# video_board_yis503.net
KiCad netlist of a schematic drawn in EAGLE
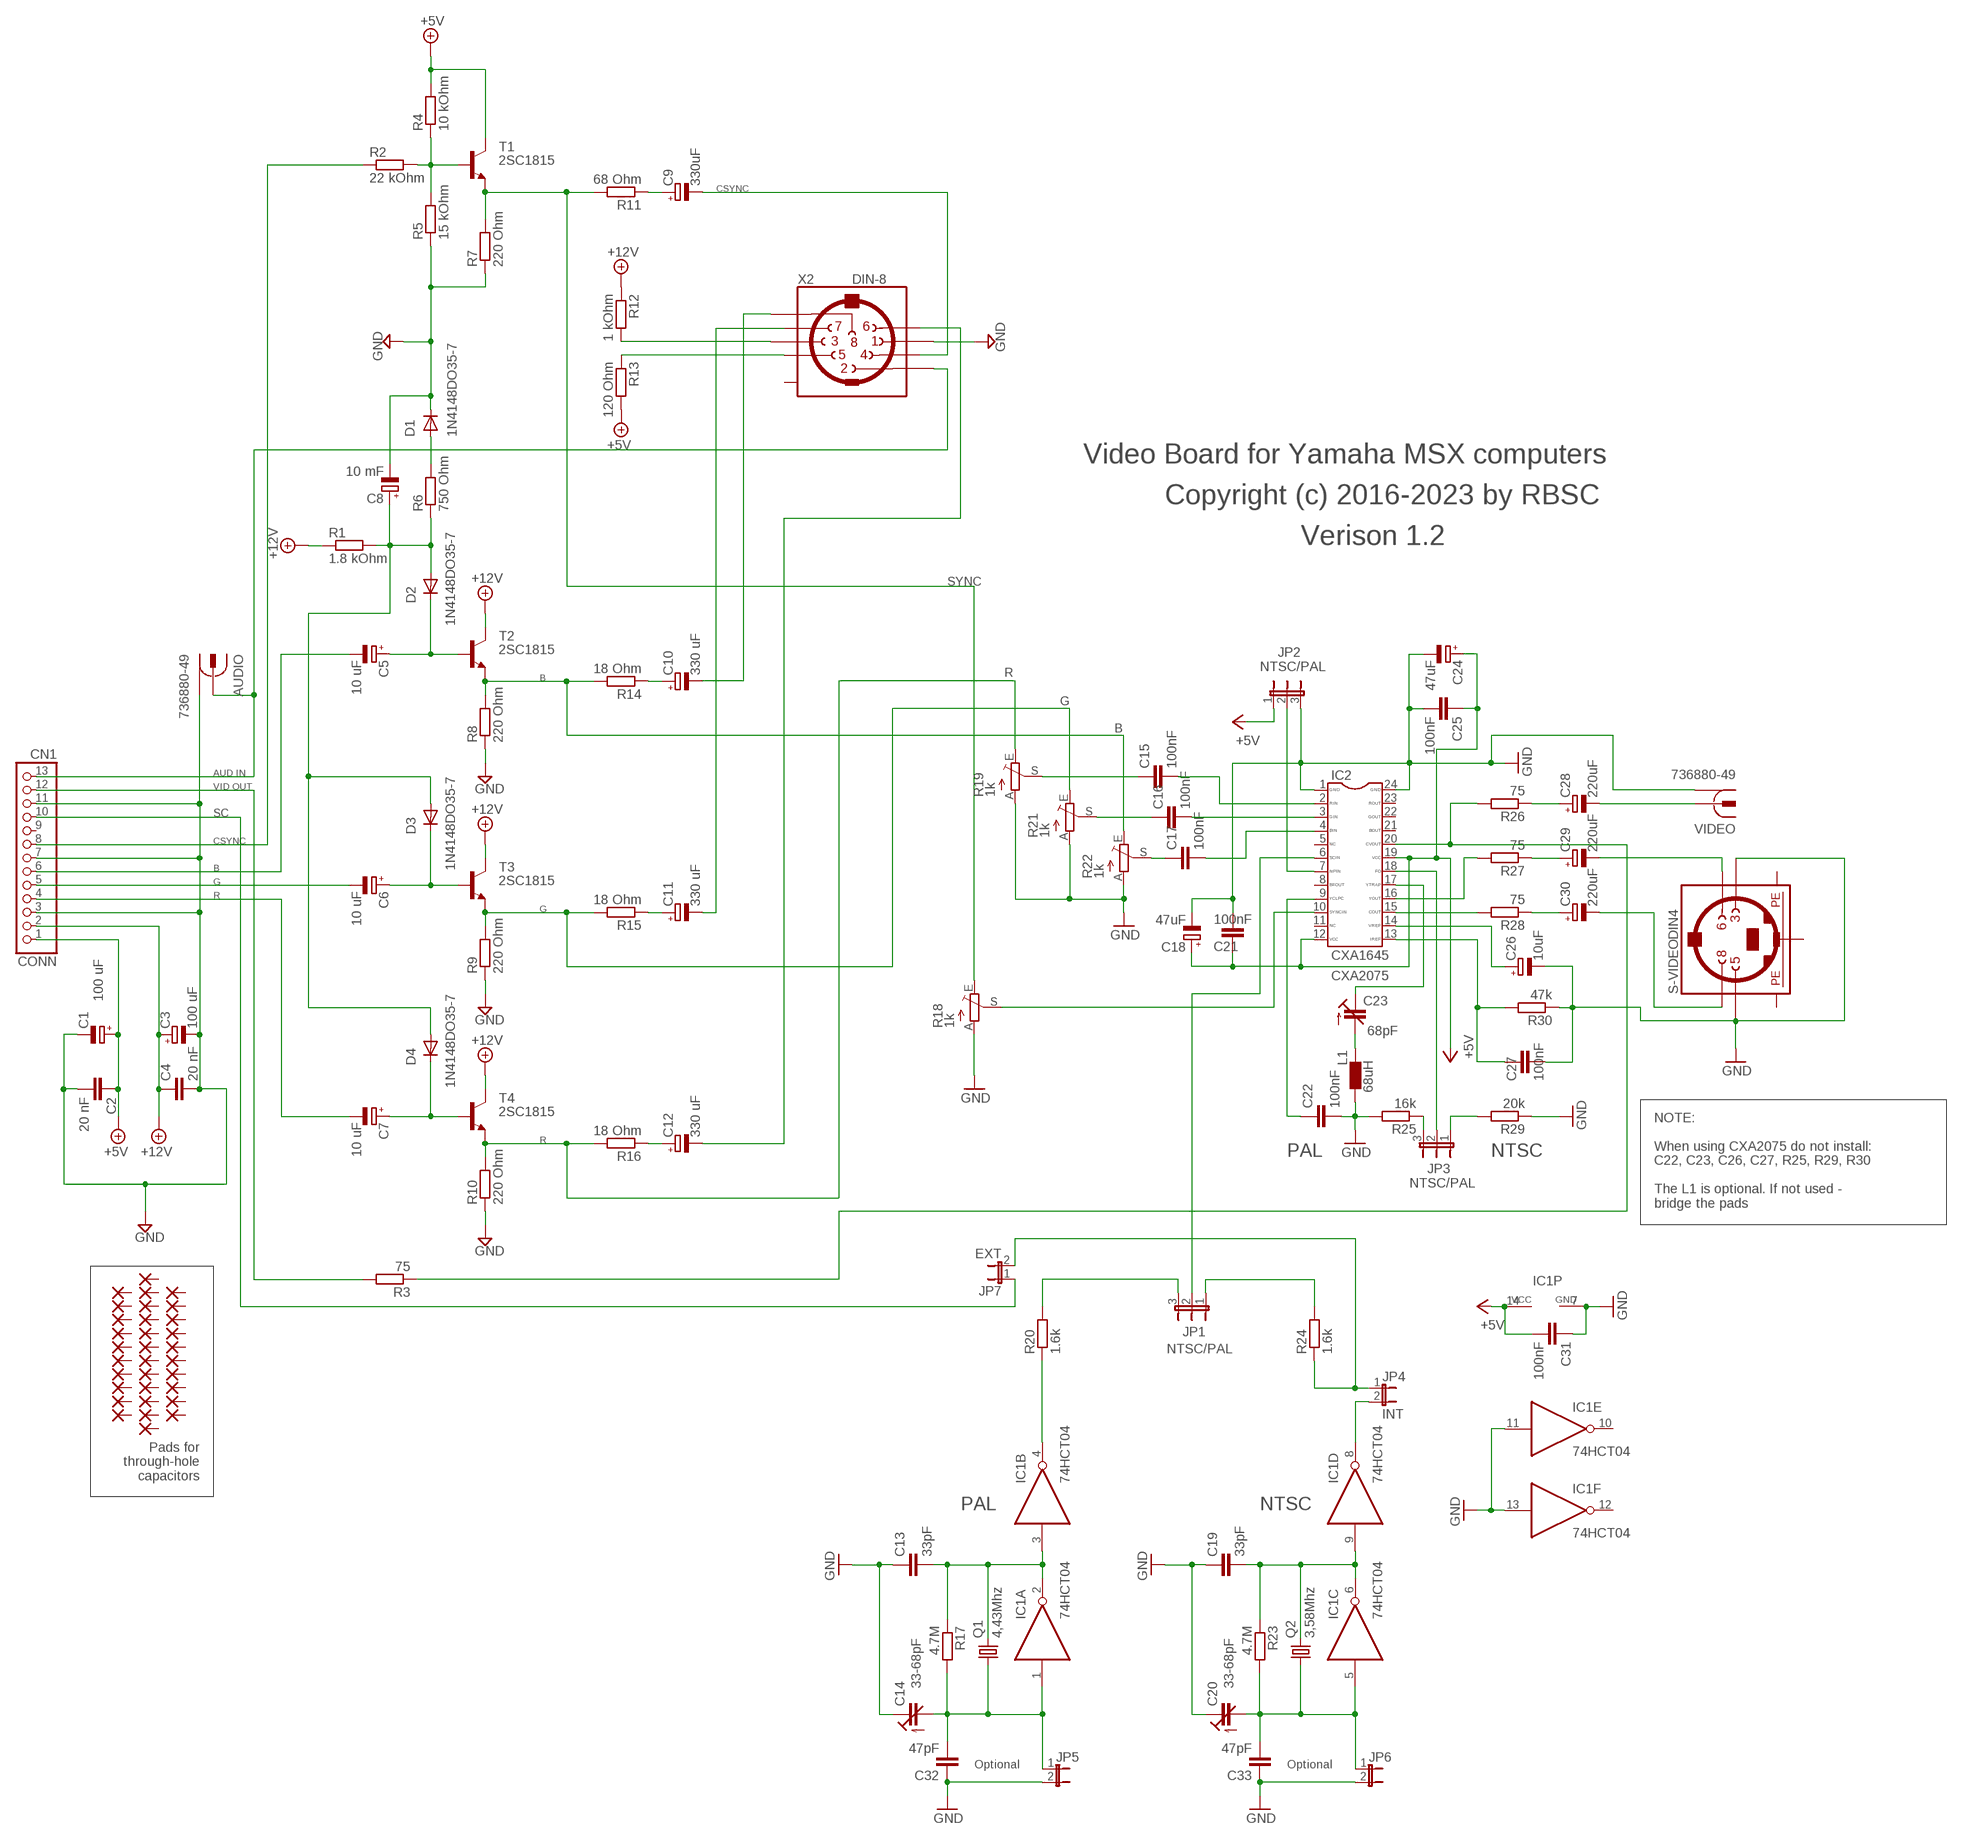
[diagram p0: schematic, sheet 1]

(export (version "E")
  (design (tool "Eeschema 10.0.6"))
  (components
    (comp (ref "AUDIO")
      (value "736880-49")
      (footprint "eagle-import:736880-49")
      (libsource (lib "eagle-import") (part "736880-49"))
    )
    (comp (ref "C1")
      (value "100 uF")
      (footprint "eagle-import:SMC_D")
      (libsource (lib "eagle-import") (part "CPOL-EUSMCD"))
    )
    (comp (ref "C2")
      (value "20 nF")
      (footprint "eagle-import:C0805")
      (libsource (lib "eagle-import") (part "C-EUC0805"))
    )
    (comp (ref "C3")
      (value "100 uF")
      (footprint "eagle-import:SMC_D")
      (libsource (lib "eagle-import") (part "CPOL-EUSMCD"))
    )
    (comp (ref "C4")
      (value "20 nF")
      (footprint "eagle-import:C0805")
      (libsource (lib "eagle-import") (part "C-EUC0805"))
    )
    (comp (ref "C5")
      (value "10 uF")
      (footprint "eagle-import:SMC_B")
      (libsource (lib "eagle-import") (part "CPOL-EUSMCB"))
    )
    (comp (ref "C6")
      (value "10 uF")
      (footprint "eagle-import:SMC_B")
      (libsource (lib "eagle-import") (part "CPOL-EUSMCB"))
    )
    (comp (ref "C7")
      (value "10 uF")
      (footprint "eagle-import:SMC_B")
      (libsource (lib "eagle-import") (part "CPOL-EUSMCB"))
    )
    (comp (ref "C8")
      (value "10 mF")
      (footprint "eagle-import:SMC_B")
      (libsource (lib "eagle-import") (part "CPOL-EUSMCB"))
    )
    (comp (ref "C9")
      (value "330uF")
      (footprint "eagle-import:SMC_D")
      (libsource (lib "eagle-import") (part "CPOL-EUSMCD"))
    )
    (comp (ref "C10")
      (value "330 uF")
      (footprint "eagle-import:SMC_D")
      (libsource (lib "eagle-import") (part "CPOL-EUSMCD"))
    )
    (comp (ref "C11")
      (value "330 uF")
      (footprint "eagle-import:SMC_D")
      (libsource (lib "eagle-import") (part "CPOL-EUSMCD"))
    )
    (comp (ref "C12")
      (value "330 uF")
      (footprint "eagle-import:SMC_D")
      (libsource (lib "eagle-import") (part "CPOL-EUSMCD"))
    )
    (comp (ref "C13")
      (value "33pF")
      (footprint "eagle-import:C0805")
      (libsource (lib "eagle-import") (part "C-EUC0805"))
    )
    (comp (ref "C14")
      (value "33-68pF")
      (footprint "eagle-import:CTRIMTZ03")
      (libsource (lib "eagle-import") (part "C-TRIMMTZ03"))
    )
    (comp (ref "C15")
      (value "100nF")
      (footprint "eagle-import:C0805")
      (libsource (lib "eagle-import") (part "C-EUC0805"))
    )
    (comp (ref "C16")
      (value "100nF")
      (footprint "eagle-import:C0805")
      (libsource (lib "eagle-import") (part "C-EUC0805"))
    )
    (comp (ref "C17")
      (value "100nF")
      (footprint "eagle-import:C0805")
      (libsource (lib "eagle-import") (part "C-EUC0805"))
    )
    (comp (ref "C18")
      (value "47uF")
      (footprint "eagle-import:SMC_B")
      (libsource (lib "eagle-import") (part "CPOL-EUSMCB"))
    )
    (comp (ref "C19")
      (value "33pF")
      (footprint "eagle-import:C0805")
      (libsource (lib "eagle-import") (part "C-EUC0805"))
    )
    (comp (ref "C20")
      (value "33-68pF")
      (footprint "eagle-import:CTRIMTZ03")
      (libsource (lib "eagle-import") (part "C-TRIMMTZ03"))
    )
    (comp (ref "C21")
      (value "100nF")
      (footprint "eagle-import:C0805")
      (libsource (lib "eagle-import") (part "C-EUC0805"))
    )
    (comp (ref "C22")
      (value "100nF")
      (footprint "eagle-import:C0805")
      (libsource (lib "eagle-import") (part "C-EUC0805"))
    )
    (comp (ref "C23")
      (value "68pF")
      (footprint "eagle-import:CTRIMTZ03")
      (libsource (lib "eagle-import") (part "C-TRIMMTZ03"))
    )
    (comp (ref "C24")
      (value "47uF")
      (footprint "eagle-import:SMC_B")
      (libsource (lib "eagle-import") (part "CPOL-EUSMCB"))
    )
    (comp (ref "C25")
      (value "100nF")
      (footprint "eagle-import:C0805")
      (libsource (lib "eagle-import") (part "C-EUC0805"))
    )
    (comp (ref "C26")
      (value "10uF")
      (footprint "eagle-import:SMC_B")
      (libsource (lib "eagle-import") (part "CPOL-EUSMCB"))
    )
    (comp (ref "C27")
      (value "100nF")
      (footprint "eagle-import:C0805")
      (libsource (lib "eagle-import") (part "C-EUC0805"))
    )
    (comp (ref "C28")
      (value "220uF")
      (footprint "eagle-import:SMC_D")
      (libsource (lib "eagle-import") (part "CPOL-EUSMCD"))
    )
    (comp (ref "C29")
      (value "220uF")
      (footprint "eagle-import:SMC_D")
      (libsource (lib "eagle-import") (part "CPOL-EUSMCD"))
    )
    (comp (ref "C30")
      (value "220uF")
      (footprint "eagle-import:SMC_D")
      (libsource (lib "eagle-import") (part "CPOL-EUSMCD"))
    )
    (comp (ref "C31")
      (value "100nF")
      (footprint "eagle-import:C0805")
      (libsource (lib "eagle-import") (part "C-EUC0805"))
    )
    (comp (ref "C32")
      (value "47pF")
      (footprint "eagle-import:C0805")
      (libsource (lib "eagle-import") (part "C-EUC0805"))
    )
    (comp (ref "C33")
      (value "47pF")
      (footprint "eagle-import:C0805")
      (libsource (lib "eagle-import") (part "C-EUC0805"))
    )
    (comp (ref "CONN")
      (value "CN1")
      (footprint "eagle-import:1X13")
      (libsource (lib "eagle-import") (part "PINHD-1X13"))
    )
    (comp (ref "D1")
      (value "1N4148DO35-7")
      (footprint "eagle-import:MINIMELF")
      (libsource (lib "eagle-import") (part "DIODE-MINIMELF"))
    )
    (comp (ref "D2")
      (value "1N4148DO35-7")
      (footprint "eagle-import:MINIMELF")
      (libsource (lib "eagle-import") (part "DIODE-MINIMELF"))
    )
    (comp (ref "D3")
      (value "1N4148DO35-7")
      (footprint "eagle-import:MINIMELF")
      (libsource (lib "eagle-import") (part "DIODE-MINIMELF"))
    )
    (comp (ref "D4")
      (value "1N4148DO35-7")
      (footprint "eagle-import:MINIMELF")
      (libsource (lib "eagle-import") (part "DIODE-MINIMELF"))
    )
    (comp (ref "IC1")
      (value "74HCT04")
      (footprint "eagle-import:SO14")
      (libsource (lib "eagle-import") (part "7404DHCT"))
    )
    (comp (ref "IC2")
      (value "CXA1645")
      (footprint "eagle-import:SOP24")
      (libsource (lib "eagle-import") (part "CXA1645"))
    )
    (comp (ref "JP1")
      (value "NTSC/PAL")
      (footprint "eagle-import:JP2")
      (libsource (lib "eagle-import") (part "JP2E"))
    )
    (comp (ref "JP2")
      (value "NTSC/PAL")
      (footprint "eagle-import:JP2")
      (libsource (lib "eagle-import") (part "JP2E"))
    )
    (comp (ref "JP3")
      (value "NTSC/PAL")
      (footprint "eagle-import:JP2")
      (libsource (lib "eagle-import") (part "JP2E"))
    )
    (comp (ref "JP4")
      (value "INT")
      (footprint "eagle-import:JP1")
      (libsource (lib "eagle-import") (part "JP1E"))
    )
    (comp (ref "JP5")
      (value "JP1E")
      (footprint "eagle-import:JP1")
      (libsource (lib "eagle-import") (part "JP1E"))
    )
    (comp (ref "JP6")
      (value "JP1E")
      (footprint "eagle-import:JP1")
      (libsource (lib "eagle-import") (part "JP1E"))
    )
    (comp (ref "JP7")
      (value "EXT")
      (footprint "eagle-import:JP1")
      (libsource (lib "eagle-import") (part "JP1E"))
    )
    (comp (ref "L1")
      (value "68uH")
      (footprint "eagle-import:L3230M")
      (libsource (lib "eagle-import") (part "LL3230M"))
    )
    (comp (ref "P1")
      (value "PADTH")
      (footprint "eagle-import:PADTH")
      (libsource (lib "eagle-import") (part "PADTH"))
    )
    (comp (ref "P2")
      (value "PADTH")
      (footprint "eagle-import:PADTH")
      (libsource (lib "eagle-import") (part "PADTH"))
    )
    (comp (ref "P3")
      (value "PADTH")
      (footprint "eagle-import:PADTH")
      (libsource (lib "eagle-import") (part "PADTH"))
    )
    (comp (ref "P4")
      (value "PADTH")
      (footprint "eagle-import:PADTH")
      (libsource (lib "eagle-import") (part "PADTH"))
    )
    (comp (ref "P5")
      (value "PADTH")
      (footprint "eagle-import:PADTH")
      (libsource (lib "eagle-import") (part "PADTH"))
    )
    (comp (ref "P6")
      (value "PADTH")
      (footprint "eagle-import:PADTH")
      (libsource (lib "eagle-import") (part "PADTH"))
    )
    (comp (ref "P7")
      (value "PADTH")
      (footprint "eagle-import:PADTH")
      (libsource (lib "eagle-import") (part "PADTH"))
    )
    (comp (ref "P8")
      (value "PADTH")
      (footprint "eagle-import:PADTH")
      (libsource (lib "eagle-import") (part "PADTH"))
    )
    (comp (ref "P9")
      (value "PADTH")
      (footprint "eagle-import:PADTH")
      (libsource (lib "eagle-import") (part "PADTH"))
    )
    (comp (ref "P10")
      (value "PADTH")
      (footprint "eagle-import:PADTH")
      (libsource (lib "eagle-import") (part "PADTH"))
    )
    (comp (ref "P11")
      (value "PADTH")
      (footprint "eagle-import:PADTH")
      (libsource (lib "eagle-import") (part "PADTH"))
    )
    (comp (ref "P12")
      (value "PADTH")
      (footprint "eagle-import:PADTH")
      (libsource (lib "eagle-import") (part "PADTH"))
    )
    (comp (ref "P13")
      (value "PADTH")
      (footprint "eagle-import:PADTH")
      (libsource (lib "eagle-import") (part "PADTH"))
    )
    (comp (ref "P14")
      (value "PADTH")
      (footprint "eagle-import:PADTH")
      (libsource (lib "eagle-import") (part "PADTH"))
    )
    (comp (ref "P15")
      (value "PADTH")
      (footprint "eagle-import:PADTH")
      (libsource (lib "eagle-import") (part "PADTH"))
    )
    (comp (ref "P16")
      (value "PADTH")
      (footprint "eagle-import:PADTH")
      (libsource (lib "eagle-import") (part "PADTH"))
    )
    (comp (ref "P17")
      (value "PADTH")
      (footprint "eagle-import:PADTH")
      (libsource (lib "eagle-import") (part "PADTH"))
    )
    (comp (ref "P18")
      (value "PADTH")
      (footprint "eagle-import:PADTH")
      (libsource (lib "eagle-import") (part "PADTH"))
    )
    (comp (ref "P19")
      (value "PADTH")
      (footprint "eagle-import:PADTH")
      (libsource (lib "eagle-import") (part "PADTH"))
    )
    (comp (ref "P20")
      (value "PADTH")
      (footprint "eagle-import:PADTH")
      (libsource (lib "eagle-import") (part "PADTH"))
    )
    (comp (ref "P21")
      (value "PADTH")
      (footprint "eagle-import:PADTH")
      (libsource (lib "eagle-import") (part "PADTH"))
    )
    (comp (ref "P22")
      (value "PADTH")
      (footprint "eagle-import:PADTH")
      (libsource (lib "eagle-import") (part "PADTH"))
    )
    (comp (ref "P23")
      (value "PADTH")
      (footprint "eagle-import:PADTH")
      (libsource (lib "eagle-import") (part "PADTH"))
    )
    (comp (ref "P24")
      (value "PADTH")
      (footprint "eagle-import:PADTH")
      (libsource (lib "eagle-import") (part "PADTH"))
    )
    (comp (ref "P25")
      (value "PADTH")
      (footprint "eagle-import:PADTH")
      (libsource (lib "eagle-import") (part "PADTH"))
    )
    (comp (ref "P26")
      (value "PADTH")
      (footprint "eagle-import:PADTH")
      (libsource (lib "eagle-import") (part "PADTH"))
    )
    (comp (ref "P27")
      (value "PADTH")
      (footprint "eagle-import:PADTH")
      (libsource (lib "eagle-import") (part "PADTH"))
    )
    (comp (ref "P28")
      (value "PADTH")
      (footprint "eagle-import:PADTH")
      (libsource (lib "eagle-import") (part "PADTH"))
    )
    (comp (ref "P29")
      (value "PADTH")
      (footprint "eagle-import:PADTH")
      (libsource (lib "eagle-import") (part "PADTH"))
    )
    (comp (ref "P30")
      (value "PADTH")
      (footprint "eagle-import:PADTH")
      (libsource (lib "eagle-import") (part "PADTH"))
    )
    (comp (ref "P31")
      (value "PADTH")
      (footprint "eagle-import:PADTH")
      (libsource (lib "eagle-import") (part "PADTH"))
    )
    (comp (ref "P32")
      (value "PADTH")
      (footprint "eagle-import:PADTH")
      (libsource (lib "eagle-import") (part "PADTH"))
    )
    (comp (ref "Q1")
      (value "4,43Mhz")
      (footprint "eagle-import:HC49_S")
      (fields (field (name "MF") "MULTICOMP") (field (name "MPN") "HC49SM-3.6864-30-50-60-16-ATF"))
      (libsource (lib "eagle-import") (part "CRYSTALHC49S"))
    )
    (comp (ref "Q2")
      (value "3,58Mhz")
      (footprint "eagle-import:HC49_S")
      (fields (field (name "MF") "MULTICOMP") (field (name "MPN") "HC49SM-3.6864-30-50-60-16-ATF"))
      (libsource (lib "eagle-import") (part "CRYSTALHC49S"))
    )
    (comp (ref "R1")
      (value "1.8 kOhm")
      (footprint "eagle-import:R0805")
      (libsource (lib "eagle-import") (part "resistor_R-EU_R0805"))
    )
    (comp (ref "R2")
      (value "22 kOhm")
      (footprint "eagle-import:R0805")
      (libsource (lib "eagle-import") (part "resistor_R-EU_R0805"))
    )
    (comp (ref "R3")
      (value "75")
      (footprint "eagle-import:R0805")
      (libsource (lib "eagle-import") (part "R-EU_R0805"))
    )
    (comp (ref "R4")
      (value "10 kOhm")
      (footprint "eagle-import:R0805")
      (libsource (lib "eagle-import") (part "resistor_R-EU_R0805"))
    )
    (comp (ref "R5")
      (value "15 kOhm")
      (footprint "eagle-import:R0805")
      (libsource (lib "eagle-import") (part "resistor_R-EU_R0805"))
    )
    (comp (ref "R6")
      (value "750 Ohm")
      (footprint "eagle-import:R0805")
      (libsource (lib "eagle-import") (part "resistor_R-EU_R0805"))
    )
    (comp (ref "R7")
      (value "220 Ohm")
      (footprint "eagle-import:R0805")
      (libsource (lib "eagle-import") (part "resistor_R-EU_R0805"))
    )
    (comp (ref "R8")
      (value "220 Ohm")
      (footprint "eagle-import:R0805")
      (libsource (lib "eagle-import") (part "resistor_R-EU_R0805"))
    )
    (comp (ref "R9")
      (value "220 Ohm")
      (footprint "eagle-import:R0805")
      (libsource (lib "eagle-import") (part "resistor_R-EU_R0805"))
    )
    (comp (ref "R10")
      (value "220 Ohm")
      (footprint "eagle-import:R0805")
      (libsource (lib "eagle-import") (part "resistor_R-EU_R0805"))
    )
    (comp (ref "R11")
      (value "68 Ohm")
      (footprint "eagle-import:R0805")
      (libsource (lib "eagle-import") (part "resistor_R-EU_R0805"))
    )
    (comp (ref "R12")
      (value "1 kOhm")
      (footprint "eagle-import:R0805")
      (libsource (lib "eagle-import") (part "resistor_R-EU_R0805"))
    )
    (comp (ref "R13")
      (value "120 Ohm")
      (footprint "eagle-import:R0805")
      (libsource (lib "eagle-import") (part "resistor_R-EU_R0805"))
    )
    (comp (ref "R14")
      (value "18 Ohm")
      (footprint "eagle-import:R0805")
      (libsource (lib "eagle-import") (part "resistor_R-EU_R0805"))
    )
    (comp (ref "R15")
      (value "18 Ohm")
      (footprint "eagle-import:R0805")
      (libsource (lib "eagle-import") (part "resistor_R-EU_R0805"))
    )
    (comp (ref "R16")
      (value "18 Ohm")
      (footprint "eagle-import:R0805")
      (libsource (lib "eagle-import") (part "resistor_R-EU_R0805"))
    )
    (comp (ref "R17")
      (value "4.7M")
      (footprint "eagle-import:R0805")
      (libsource (lib "eagle-import") (part "R-EU_R0805"))
    )
    (comp (ref "R18")
      (value "1k")
      (footprint "eagle-import:CA6V")
      (libsource (lib "eagle-import") (part "TRIM_EU-CA6V"))
    )
    (comp (ref "R19")
      (value "1k")
      (footprint "eagle-import:CA6V")
      (libsource (lib "eagle-import") (part "TRIM_EU-CA6V"))
    )
    (comp (ref "R20")
      (value "1.6k")
      (footprint "eagle-import:R0805")
      (libsource (lib "eagle-import") (part "R-EU_R0805"))
    )
    (comp (ref "R21")
      (value "1k")
      (footprint "eagle-import:CA6V")
      (libsource (lib "eagle-import") (part "TRIM_EU-CA6V"))
    )
    (comp (ref "R22")
      (value "1k")
      (footprint "eagle-import:CA6V")
      (libsource (lib "eagle-import") (part "TRIM_EU-CA6V"))
    )
    (comp (ref "R23")
      (value "4.7M")
      (footprint "eagle-import:R0805")
      (libsource (lib "eagle-import") (part "R-EU_R0805"))
    )
    (comp (ref "R24")
      (value "1.6k")
      (footprint "eagle-import:R0805")
      (libsource (lib "eagle-import") (part "R-EU_R0805"))
    )
    (comp (ref "R25")
      (value "16k")
      (footprint "eagle-import:R0805")
      (libsource (lib "eagle-import") (part "R-EU_R0805"))
    )
    (comp (ref "R26")
      (value "75")
      (footprint "eagle-import:R0805")
      (libsource (lib "eagle-import") (part "R-EU_R0805"))
    )
    (comp (ref "R27")
      (value "75")
      (footprint "eagle-import:R0805")
      (libsource (lib "eagle-import") (part "R-EU_R0805"))
    )
    (comp (ref "R28")
      (value "75")
      (footprint "eagle-import:R0805")
      (libsource (lib "eagle-import") (part "R-EU_R0805"))
    )
    (comp (ref "R29")
      (value "20k")
      (footprint "eagle-import:R0805")
      (libsource (lib "eagle-import") (part "R-EU_R0805"))
    )
    (comp (ref "R30")
      (value "47k")
      (footprint "eagle-import:R0805")
      (libsource (lib "eagle-import") (part "R-EU_R0805"))
    )
    (comp (ref "S-VIDEO")
      (value "DIN4")
      (footprint "eagle-import:M_DIN4")
      (libsource (lib "eagle-import") (part "MINI_DIN_4"))
    )
    (comp (ref "T1")
      (value "2SC1815")
      (footprint "eagle-import:TO92-ECB")
      (libsource (lib "eagle-import") (part "2SC1815"))
    )
    (comp (ref "T2")
      (value "2SC1815")
      (footprint "eagle-import:TO92-ECB")
      (libsource (lib "eagle-import") (part "2SC1815"))
    )
    (comp (ref "T3")
      (value "2SC1815")
      (footprint "eagle-import:TO92-ECB")
      (libsource (lib "eagle-import") (part "2SC1815"))
    )
    (comp (ref "T4")
      (value "2SC1815")
      (footprint "eagle-import:TO92-ECB")
      (libsource (lib "eagle-import") (part "2SC1815"))
    )
    (comp (ref "VIDEO")
      (value "736880-49")
      (footprint "eagle-import:736880-49")
      (libsource (lib "eagle-import") (part "736880-49"))
    )
    (comp (ref "X2")
      (value "DIN-8")
      (footprint "eagle-import:DIN8")
      (libsource (lib "eagle-import") (part "DIN-8"))
    )
  )
  (nets
    (net (code "1") (name "+5V") (class "Default")
      (node (ref "C1") (pin "+") (pinfunction "+_+") (pintype "passive"))
      (node (ref "C18") (pin "+") (pinfunction "+_+") (pintype "passive"))
      (node (ref "C2") (pin "1") (pinfunction "1_1") (pintype "passive"))
      (node (ref "C21") (pin "1") (pinfunction "1_1") (pintype "passive"))
      (node (ref "C24") (pin "+") (pinfunction "+_+") (pintype "passive"))
      (node (ref "C25") (pin "1") (pinfunction "1_1") (pintype "passive"))
      (node (ref "C31") (pin "2") (pinfunction "2_2") (pintype "passive"))
      (node (ref "CONN") (pin "1") (pinfunction "1_1") (pintype "passive"))
      (node (ref "IC1") (pin "14") (pinfunction "VCC_14") (pintype "power_in"))
      (node (ref "IC2") (pin "12") (pinfunction "12_12") (pintype "passive"))
      (node (ref "IC2") (pin "19") (pinfunction "19_19") (pintype "passive"))
      (node (ref "JP2") (pin "1") (pinfunction "1_1") (pintype "passive"))
      (node (ref "R13") (pin "2") (pinfunction "2_2") (pintype "passive"))
      (node (ref "R4") (pin "2") (pinfunction "2_2") (pintype "passive"))
      (node (ref "T1") (pin "C") (pinfunction "C_C") (pintype "passive"))
    )
    (net (code "2") (name "+12V") (class "Default")
      (node (ref "C3") (pin "+") (pinfunction "+_+") (pintype "passive"))
      (node (ref "C4") (pin "1") (pinfunction "1_1") (pintype "passive"))
      (node (ref "CONN") (pin "2") (pinfunction "2_2") (pintype "passive"))
      (node (ref "R1") (pin "1") (pinfunction "1_1") (pintype "passive"))
      (node (ref "R12") (pin "1") (pinfunction "1_1") (pintype "passive"))
      (node (ref "T2") (pin "C") (pinfunction "C_C") (pintype "passive"))
      (node (ref "T3") (pin "C") (pinfunction "C_C") (pintype "passive"))
      (node (ref "T4") (pin "C") (pinfunction "C_C") (pintype "passive"))
    )
    (net (code "3") (name "/PE1") (class "Default")
      (node (ref "S-VIDEO") (pin "SH1") (pinfunction "PE1_SH1") (pintype "power_in"))
    )
    (net (code "4") (name "/PE2") (class "Default")
      (node (ref "S-VIDEO") (pin "SH2") (pinfunction "PE2_SH2") (pintype "power_in"))
    )
    (net (code "5") (name "/PE3") (class "Default")
      (node (ref "S-VIDEO") (pin "SH3") (pinfunction "PE3_SH3") (pintype "power_in"))
    )
    (net (code "6") (name "/SC") (class "Default")
      (node (ref "CONN") (pin "10") (pinfunction "10_10") (pintype "passive"))
      (node (ref "JP7") (pin "1") (pinfunction "1_1") (pintype "passive"))
    )
    (net (code "7") (name "GND") (class "Default")
      (node (ref "AUDIO") (pin "1") (pinfunction "1_1") (pintype "passive"))
      (node (ref "AUDIO") (pin "1@1") (pinfunction "1_1@1") (pintype "passive"))
      (node (ref "AUDIO") (pin "1@2") (pinfunction "1_1@2") (pintype "passive"))
      (node (ref "C1") (pin "-") (pinfunction "-_-") (pintype "passive"))
      (node (ref "C13") (pin "1") (pinfunction "1_1") (pintype "passive"))
      (node (ref "C14") (pin "1") (pinfunction "E_1") (pintype "passive"))
      (node (ref "C18") (pin "-") (pinfunction "-_-") (pintype "passive"))
      (node (ref "C19") (pin "1") (pinfunction "1_1") (pintype "passive"))
      (node (ref "C2") (pin "2") (pinfunction "2_2") (pintype "passive"))
      (node (ref "C20") (pin "1") (pinfunction "E_1") (pintype "passive"))
      (node (ref "C21") (pin "2") (pinfunction "2_2") (pintype "passive"))
      (node (ref "C22") (pin "2") (pinfunction "2_2") (pintype "passive"))
      (node (ref "C24") (pin "-") (pinfunction "-_-") (pintype "passive"))
      (node (ref "C25") (pin "2") (pinfunction "2_2") (pintype "passive"))
      (node (ref "C26") (pin "-") (pinfunction "-_-") (pintype "passive"))
      (node (ref "C27") (pin "2") (pinfunction "2_2") (pintype "passive"))
      (node (ref "C3") (pin "-") (pinfunction "-_-") (pintype "passive"))
      (node (ref "C31") (pin "1") (pinfunction "1_1") (pintype "passive"))
      (node (ref "C32") (pin "1") (pinfunction "1_1") (pintype "passive"))
      (node (ref "C33") (pin "1") (pinfunction "1_1") (pintype "passive"))
      (node (ref "C4") (pin "2") (pinfunction "2_2") (pintype "passive"))
      (node (ref "C8") (pin "-") (pinfunction "-_-") (pintype "passive"))
      (node (ref "CONN") (pin "11") (pinfunction "11_11") (pintype "passive"))
      (node (ref "CONN") (pin "3") (pinfunction "3_3") (pintype "passive"))
      (node (ref "CONN") (pin "7") (pinfunction "7_7") (pintype "passive"))
      (node (ref "D1") (pin "C") (pinfunction "C_C") (pintype "passive"))
      (node (ref "IC1") (pin "11") (pinfunction "I_11") (pintype "input"))
      (node (ref "IC1") (pin "13") (pinfunction "I_13") (pintype "input"))
      (node (ref "IC1") (pin "7") (pinfunction "GND_7") (pintype "power_in"))
      (node (ref "IC2") (pin "1") (pinfunction "1_1") (pintype "passive"))
      (node (ref "IC2") (pin "24") (pinfunction "24_24") (pintype "passive"))
      (node (ref "JP2") (pin "3") (pinfunction "3_3") (pintype "passive"))
      (node (ref "JP5") (pin "2") (pinfunction "2_2") (pintype "passive"))
      (node (ref "JP6") (pin "2") (pinfunction "2_2") (pintype "passive"))
      (node (ref "L1") (pin "2") (pinfunction "2_2") (pintype "passive"))
      (node (ref "R10") (pin "1") (pinfunction "1_1") (pintype "passive"))
      (node (ref "R18") (pin "A") (pinfunction "A_A") (pintype "passive"))
      (node (ref "R19") (pin "A") (pinfunction "A_A") (pintype "passive"))
      (node (ref "R21") (pin "A") (pinfunction "A_A") (pintype "passive"))
      (node (ref "R22") (pin "A") (pinfunction "A_A") (pintype "passive"))
      (node (ref "R25") (pin "2") (pinfunction "2_2") (pintype "passive"))
      (node (ref "R29") (pin "1") (pinfunction "1_1") (pintype "passive"))
      (node (ref "R30") (pin "1") (pinfunction "1_1") (pintype "passive"))
      (node (ref "R5") (pin "1") (pinfunction "1_1") (pintype "passive"))
      (node (ref "R7") (pin "1") (pinfunction "1_1") (pintype "passive"))
      (node (ref "R8") (pin "1") (pinfunction "1_1") (pintype "passive"))
      (node (ref "R9") (pin "1") (pinfunction "1_1") (pintype "passive"))
      (node (ref "S-VIDEO") (pin "3") (pinfunction "3_3") (pintype "passive"))
      (node (ref "S-VIDEO") (pin "5") (pinfunction "5_5") (pintype "passive"))
      (node (ref "VIDEO") (pin "1") (pinfunction "1_1") (pintype "passive"))
      (node (ref "VIDEO") (pin "1@1") (pinfunction "1_1@1") (pintype "passive"))
      (node (ref "VIDEO") (pin "1@2") (pinfunction "1_1@2") (pintype "passive"))
      (node (ref "X2") (pin "1") (pinfunction "1_1") (pintype "passive"))
    )
    (net (code "8") (name "Net-(AUDIO-Pad2)") (class "Default")
      (node (ref "AUDIO") (pin "2") (pinfunction "2_2") (pintype "passive"))
      (node (ref "CONN") (pin "13") (pinfunction "13_13") (pintype "passive"))
      (node (ref "X2") (pin "2") (pinfunction "2_2") (pintype "passive"))
    )
    (net (code "9") (name "Net-(C5-Pad+)") (class "Default")
      (node (ref "C5") (pin "+") (pinfunction "+_+") (pintype "passive"))
      (node (ref "D2") (pin "C") (pinfunction "C_C") (pintype "passive"))
      (node (ref "T2") (pin "B") (pinfunction "B_B") (pintype "passive"))
    )
    (net (code "10") (name "Net-(C5-Pad-)") (class "Default")
      (node (ref "C5") (pin "-") (pinfunction "-_-") (pintype "passive"))
      (node (ref "CONN") (pin "6") (pinfunction "6_6") (pintype "passive"))
    )
    (net (code "11") (name "Net-(C6-Pad+)") (class "Default")
      (node (ref "C6") (pin "+") (pinfunction "+_+") (pintype "passive"))
      (node (ref "D3") (pin "C") (pinfunction "C_C") (pintype "passive"))
      (node (ref "T3") (pin "B") (pinfunction "B_B") (pintype "passive"))
    )
    (net (code "12") (name "Net-(C6-Pad-)") (class "Default")
      (node (ref "C6") (pin "-") (pinfunction "-_-") (pintype "passive"))
      (node (ref "CONN") (pin "5") (pinfunction "5_5") (pintype "passive"))
    )
    (net (code "13") (name "Net-(C7-Pad+)") (class "Default")
      (node (ref "C7") (pin "+") (pinfunction "+_+") (pintype "passive"))
      (node (ref "D4") (pin "C") (pinfunction "C_C") (pintype "passive"))
      (node (ref "T4") (pin "B") (pinfunction "B_B") (pintype "passive"))
    )
    (net (code "14") (name "Net-(C7-Pad-)") (class "Default")
      (node (ref "C7") (pin "-") (pinfunction "-_-") (pintype "passive"))
      (node (ref "CONN") (pin "4") (pinfunction "4_4") (pintype "passive"))
    )
    (net (code "15") (name "Net-(C8-Pad+)") (class "Default")
      (node (ref "C8") (pin "+") (pinfunction "+_+") (pintype "passive"))
      (node (ref "D2") (pin "A") (pinfunction "A_A") (pintype "passive"))
      (node (ref "D3") (pin "A") (pinfunction "A_A") (pintype "passive"))
      (node (ref "D4") (pin "A") (pinfunction "A_A") (pintype "passive"))
      (node (ref "R1") (pin "2") (pinfunction "2_2") (pintype "passive"))
      (node (ref "R6") (pin "1") (pinfunction "1_1") (pintype "passive"))
    )
    (net (code "16") (name "Net-(C9-Pad+)") (class "Default")
      (node (ref "C9") (pin "+") (pinfunction "+_+") (pintype "passive"))
      (node (ref "R11") (pin "1") (pinfunction "1_1") (pintype "passive"))
    )
    (net (code "17") (name "Net-(C9-Pad-)") (class "Default")
      (node (ref "C9") (pin "-") (pinfunction "-_-") (pintype "passive"))
      (node (ref "X2") (pin "4") (pinfunction "4_4") (pintype "passive"))
    )
    (net (code "18") (name "Net-(C10-Pad+)") (class "Default")
      (node (ref "C10") (pin "+") (pinfunction "+_+") (pintype "passive"))
      (node (ref "R14") (pin "1") (pinfunction "1_1") (pintype "passive"))
    )
    (net (code "19") (name "Net-(C10-Pad-)") (class "Default")
      (node (ref "C10") (pin "-") (pinfunction "-_-") (pintype "passive"))
      (node (ref "X2") (pin "8") (pinfunction "8_8") (pintype "passive"))
    )
    (net (code "20") (name "Net-(C11-Pad+)") (class "Default")
      (node (ref "C11") (pin "+") (pinfunction "+_+") (pintype "passive"))
      (node (ref "R15") (pin "1") (pinfunction "1_1") (pintype "passive"))
    )
    (net (code "21") (name "Net-(C11-Pad-)") (class "Default")
      (node (ref "C11") (pin "-") (pinfunction "-_-") (pintype "passive"))
      (node (ref "X2") (pin "7") (pinfunction "7_7") (pintype "passive"))
    )
    (net (code "22") (name "Net-(C12-Pad+)") (class "Default")
      (node (ref "C12") (pin "+") (pinfunction "+_+") (pintype "passive"))
      (node (ref "R16") (pin "1") (pinfunction "1_1") (pintype "passive"))
    )
    (net (code "23") (name "Net-(C12-Pad-)") (class "Default")
      (node (ref "C12") (pin "-") (pinfunction "-_-") (pintype "passive"))
      (node (ref "X2") (pin "6") (pinfunction "6_6") (pintype "passive"))
    )
    (net (code "24") (name "Net-(C14-A)") (class "Default")
      (node (ref "C14") (pin "2") (pinfunction "A_2") (pintype "passive"))
      (node (ref "C32") (pin "2") (pinfunction "2_2") (pintype "passive"))
      (node (ref "IC1") (pin "1") (pinfunction "I_1") (pintype "input"))
      (node (ref "JP5") (pin "1") (pinfunction "1_1") (pintype "passive"))
      (node (ref "Q1") (pin "1") (pinfunction "1_1") (pintype "passive"))
      (node (ref "R17") (pin "2") (pinfunction "2_2") (pintype "passive"))
    )
    (net (code "25") (name "Net-(C15-Pad1)") (class "Default")
      (node (ref "C15") (pin "1") (pinfunction "1_1") (pintype "passive"))
      (node (ref "R19") (pin "S") (pinfunction "S_S") (pintype "passive"))
    )
    (net (code "26") (name "Net-(C15-Pad2)") (class "Default")
      (node (ref "C15") (pin "2") (pinfunction "2_2") (pintype "passive"))
      (node (ref "IC2") (pin "2") (pinfunction "2_2") (pintype "passive"))
    )
    (net (code "27") (name "Net-(C16-Pad1)") (class "Default")
      (node (ref "C16") (pin "1") (pinfunction "1_1") (pintype "passive"))
      (node (ref "R21") (pin "S") (pinfunction "S_S") (pintype "passive"))
    )
    (net (code "28") (name "Net-(C16-Pad2)") (class "Default")
      (node (ref "C16") (pin "2") (pinfunction "2_2") (pintype "passive"))
      (node (ref "IC2") (pin "3") (pinfunction "3_3") (pintype "passive"))
    )
    (net (code "29") (name "Net-(C17-Pad1)") (class "Default")
      (node (ref "C17") (pin "1") (pinfunction "1_1") (pintype "passive"))
      (node (ref "R22") (pin "S") (pinfunction "S_S") (pintype "passive"))
    )
    (net (code "30") (name "Net-(C17-Pad2)") (class "Default")
      (node (ref "C17") (pin "2") (pinfunction "2_2") (pintype "passive"))
      (node (ref "IC2") (pin "4") (pinfunction "4_4") (pintype "passive"))
    )
    (net (code "31") (name "Net-(C20-A)") (class "Default")
      (node (ref "C20") (pin "2") (pinfunction "A_2") (pintype "passive"))
      (node (ref "C33") (pin "2") (pinfunction "2_2") (pintype "passive"))
      (node (ref "IC1") (pin "5") (pinfunction "I_5") (pintype "input"))
      (node (ref "JP6") (pin "1") (pinfunction "1_1") (pintype "passive"))
      (node (ref "Q2") (pin "1") (pinfunction "1_1") (pintype "passive"))
      (node (ref "R23") (pin "2") (pinfunction "2_2") (pintype "passive"))
    )
    (net (code "32") (name "Net-(C22-Pad1)") (class "Default")
      (node (ref "C22") (pin "1") (pinfunction "1_1") (pintype "passive"))
      (node (ref "IC2") (pin "9") (pinfunction "9_9") (pintype "passive"))
    )
    (net (code "33") (name "Net-(C23-A)") (class "Default")
      (node (ref "C23") (pin "2") (pinfunction "A_2") (pintype "passive"))
      (node (ref "L1") (pin "1") (pinfunction "1_1") (pintype "passive"))
    )
    (net (code "34") (name "Net-(C23-E)") (class "Default")
      (node (ref "C23") (pin "1") (pinfunction "E_1") (pintype "passive"))
      (node (ref "IC2") (pin "17") (pinfunction "17_17") (pintype "passive"))
    )
    (net (code "35") (name "Net-(C26-Pad+)") (class "Default")
      (node (ref "C26") (pin "+") (pinfunction "+_+") (pintype "passive"))
      (node (ref "IC2") (pin "14") (pinfunction "14_14") (pintype "passive"))
    )
    (net (code "36") (name "Net-(C27-Pad1)") (class "Default")
      (node (ref "C27") (pin "1") (pinfunction "1_1") (pintype "passive"))
      (node (ref "IC2") (pin "13") (pinfunction "13_13") (pintype "passive"))
      (node (ref "R30") (pin "2") (pinfunction "2_2") (pintype "passive"))
    )
    (net (code "37") (name "Net-(C28-Pad+)") (class "Default")
      (node (ref "C28") (pin "+") (pinfunction "+_+") (pintype "passive"))
      (node (ref "R26") (pin "1") (pinfunction "1_1") (pintype "passive"))
    )
    (net (code "38") (name "Net-(C28-Pad-)") (class "Default")
      (node (ref "C28") (pin "-") (pinfunction "-_-") (pintype "passive"))
      (node (ref "VIDEO") (pin "2") (pinfunction "2_2") (pintype "passive"))
    )
    (net (code "39") (name "Net-(C29-Pad+)") (class "Default")
      (node (ref "C29") (pin "+") (pinfunction "+_+") (pintype "passive"))
      (node (ref "R27") (pin "1") (pinfunction "1_1") (pintype "passive"))
    )
    (net (code "40") (name "Net-(C29-Pad-)") (class "Default")
      (node (ref "C29") (pin "-") (pinfunction "-_-") (pintype "passive"))
      (node (ref "S-VIDEO") (pin "6") (pinfunction "6_6") (pintype "passive"))
    )
    (net (code "41") (name "Net-(C30-Pad+)") (class "Default")
      (node (ref "C30") (pin "+") (pinfunction "+_+") (pintype "passive"))
      (node (ref "R28") (pin "1") (pinfunction "1_1") (pintype "passive"))
    )
    (net (code "42") (name "Net-(C30-Pad-)") (class "Default")
      (node (ref "C30") (pin "-") (pinfunction "-_-") (pintype "passive"))
      (node (ref "S-VIDEO") (pin "8") (pinfunction "8_8") (pintype "passive"))
    )
    (net (code "43") (name "Net-(CONN-Pad8)") (class "Default")
      (node (ref "CONN") (pin "8") (pinfunction "8_8") (pintype "passive"))
      (node (ref "R2") (pin "1") (pinfunction "1_1") (pintype "passive"))
    )
    (net (code "44") (name "Net-(CONN-Pad12)") (class "Default")
      (node (ref "CONN") (pin "12") (pinfunction "12_12") (pintype "passive"))
      (node (ref "R3") (pin "2") (pinfunction "2_2") (pintype "passive"))
    )
    (net (code "45") (name "Net-(D1-PadA)") (class "Default")
      (node (ref "D1") (pin "A") (pinfunction "A_A") (pintype "passive"))
      (node (ref "R6") (pin "2") (pinfunction "2_2") (pintype "passive"))
    )
    (net (code "46") (name "Net-(IC1A-O)") (class "Default")
      (node (ref "C13") (pin "2") (pinfunction "2_2") (pintype "passive"))
      (node (ref "IC1") (pin "2") (pinfunction "O_2") (pintype "output"))
      (node (ref "IC1") (pin "3") (pinfunction "I_3") (pintype "input"))
      (node (ref "Q1") (pin "2") (pinfunction "2_2") (pintype "passive"))
      (node (ref "R17") (pin "1") (pinfunction "1_1") (pintype "passive"))
    )
    (net (code "47") (name "Net-(IC1B-O)") (class "Default")
      (node (ref "IC1") (pin "4") (pinfunction "O_4") (pintype "output"))
      (node (ref "R20") (pin "1") (pinfunction "1_1") (pintype "passive"))
    )
    (net (code "48") (name "Net-(IC1C-O)") (class "Default")
      (node (ref "C19") (pin "2") (pinfunction "2_2") (pintype "passive"))
      (node (ref "IC1") (pin "6") (pinfunction "O_6") (pintype "output"))
      (node (ref "IC1") (pin "9") (pinfunction "I_9") (pintype "input"))
      (node (ref "Q2") (pin "2") (pinfunction "2_2") (pintype "passive"))
      (node (ref "R23") (pin "1") (pinfunction "1_1") (pintype "passive"))
    )
    (net (code "49") (name "Net-(IC1D-O)") (class "Default")
      (node (ref "IC1") (pin "8") (pinfunction "O_8") (pintype "output"))
      (node (ref "JP4") (pin "2") (pinfunction "2_2") (pintype "passive"))
    )
    (net (code "50") (name "Net-(IC2-Pad6)") (class "Default")
      (node (ref "IC2") (pin "6") (pinfunction "6_6") (pintype "passive"))
      (node (ref "JP1") (pin "2") (pinfunction "2_2") (pintype "passive"))
    )
    (net (code "51") (name "Net-(IC2-Pad7)") (class "Default")
      (node (ref "IC2") (pin "7") (pinfunction "7_7") (pintype "passive"))
      (node (ref "JP2") (pin "2") (pinfunction "2_2") (pintype "passive"))
    )
    (net (code "52") (name "Net-(IC2-Pad10)") (class "Default")
      (node (ref "IC2") (pin "10") (pinfunction "10_10") (pintype "passive"))
      (node (ref "R18") (pin "S") (pinfunction "S_S") (pintype "passive"))
    )
    (net (code "53") (name "Net-(IC2-Pad15)") (class "Default")
      (node (ref "IC2") (pin "15") (pinfunction "15_15") (pintype "passive"))
      (node (ref "R28") (pin "2") (pinfunction "2_2") (pintype "passive"))
    )
    (net (code "54") (name "Net-(IC2-Pad16)") (class "Default")
      (node (ref "IC2") (pin "16") (pinfunction "16_16") (pintype "passive"))
      (node (ref "R27") (pin "2") (pinfunction "2_2") (pintype "passive"))
    )
    (net (code "55") (name "Net-(IC2-Pad18)") (class "Default")
      (node (ref "IC2") (pin "18") (pinfunction "18_18") (pintype "passive"))
      (node (ref "JP3") (pin "2") (pinfunction "2_2") (pintype "passive"))
    )
    (net (code "56") (name "Net-(IC2-Pad20)") (class "Default")
      (node (ref "IC2") (pin "20") (pinfunction "20_20") (pintype "passive"))
      (node (ref "R26") (pin "2") (pinfunction "2_2") (pintype "passive"))
      (node (ref "R3") (pin "1") (pinfunction "1_1") (pintype "passive"))
    )
    (net (code "57") (name "Net-(JP1-Pad1)") (class "Default")
      (node (ref "JP1") (pin "1") (pinfunction "1_1") (pintype "passive"))
      (node (ref "R24") (pin "2") (pinfunction "2_2") (pintype "passive"))
    )
    (net (code "58") (name "Net-(JP1-Pad3)") (class "Default")
      (node (ref "JP1") (pin "3") (pinfunction "3_3") (pintype "passive"))
      (node (ref "R20") (pin "2") (pinfunction "2_2") (pintype "passive"))
    )
    (net (code "59") (name "Net-(JP3-Pad1)") (class "Default")
      (node (ref "JP3") (pin "1") (pinfunction "1_1") (pintype "passive"))
      (node (ref "R29") (pin "2") (pinfunction "2_2") (pintype "passive"))
    )
    (net (code "60") (name "Net-(JP3-Pad3)") (class "Default")
      (node (ref "JP3") (pin "3") (pinfunction "3_3") (pintype "passive"))
      (node (ref "R25") (pin "1") (pinfunction "1_1") (pintype "passive"))
    )
    (net (code "61") (name "Net-(JP4-Pad1)") (class "Default")
      (node (ref "JP4") (pin "1") (pinfunction "1_1") (pintype "passive"))
      (node (ref "JP7") (pin "2") (pinfunction "2_2") (pintype "passive"))
      (node (ref "R24") (pin "1") (pinfunction "1_1") (pintype "passive"))
    )
    (net (code "62") (name "Net-(R2-Pad2)") (class "Default")
      (node (ref "R2") (pin "2") (pinfunction "2_2") (pintype "passive"))
      (node (ref "R4") (pin "1") (pinfunction "1_1") (pintype "passive"))
      (node (ref "R5") (pin "2") (pinfunction "2_2") (pintype "passive"))
      (node (ref "T1") (pin "B") (pinfunction "B_B") (pintype "passive"))
    )
    (net (code "63") (name "Net-(R10-Pad2)") (class "Default")
      (node (ref "R10") (pin "2") (pinfunction "2_2") (pintype "passive"))
      (node (ref "R16") (pin "2") (pinfunction "2_2") (pintype "passive"))
      (node (ref "R19") (pin "E") (pinfunction "E_E") (pintype "passive"))
      (node (ref "T4") (pin "E") (pinfunction "E_E") (pintype "passive"))
    )
    (net (code "64") (name "Net-(R11-Pad2)") (class "Default")
      (node (ref "R11") (pin "2") (pinfunction "2_2") (pintype "passive"))
      (node (ref "R18") (pin "E") (pinfunction "E_E") (pintype "passive"))
      (node (ref "R7") (pin "2") (pinfunction "2_2") (pintype "passive"))
      (node (ref "T1") (pin "E") (pinfunction "E_E") (pintype "passive"))
    )
    (net (code "65") (name "Net-(R12-Pad2)") (class "Default")
      (node (ref "R12") (pin "2") (pinfunction "2_2") (pintype "passive"))
      (node (ref "X2") (pin "3") (pinfunction "3_3") (pintype "passive"))
    )
    (net (code "66") (name "Net-(R13-Pad1)") (class "Default")
      (node (ref "R13") (pin "1") (pinfunction "1_1") (pintype "passive"))
      (node (ref "X2") (pin "5") (pinfunction "5_5") (pintype "passive"))
    )
    (net (code "67") (name "Net-(R14-Pad2)") (class "Default")
      (node (ref "R14") (pin "2") (pinfunction "2_2") (pintype "passive"))
      (node (ref "R22") (pin "E") (pinfunction "E_E") (pintype "passive"))
      (node (ref "R8") (pin "2") (pinfunction "2_2") (pintype "passive"))
      (node (ref "T2") (pin "E") (pinfunction "E_E") (pintype "passive"))
    )
    (net (code "68") (name "Net-(R15-Pad2)") (class "Default")
      (node (ref "R15") (pin "2") (pinfunction "2_2") (pintype "passive"))
      (node (ref "R21") (pin "E") (pinfunction "E_E") (pintype "passive"))
      (node (ref "R9") (pin "2") (pinfunction "2_2") (pintype "passive"))
      (node (ref "T3") (pin "E") (pinfunction "E_E") (pintype "passive"))
    )
    (net (code "69") (name "unconnected-(CONN-Pad9)") (class "Default")
      (node (ref "CONN") (pin "9") (pinfunction "9_9") (pintype "passive"))
    )
    (net (code "70") (name "unconnected-(IC1E-O-Pad10)") (class "Default")
      (node (ref "IC1") (pin "10") (pinfunction "O_10") (pintype "output"))
    )
    (net (code "71") (name "unconnected-(IC1F-O-Pad12)") (class "Default")
      (node (ref "IC1") (pin "12") (pinfunction "O_12") (pintype "output"))
    )
    (net (code "72") (name "unconnected-(IC2-Pad5)") (class "Default")
      (node (ref "IC2") (pin "5") (pinfunction "5_5") (pintype "passive"))
    )
    (net (code "73") (name "unconnected-(IC2-Pad8)") (class "Default")
      (node (ref "IC2") (pin "8") (pinfunction "8_8") (pintype "passive"))
    )
    (net (code "74") (name "unconnected-(IC2-Pad11)") (class "Default")
      (node (ref "IC2") (pin "11") (pinfunction "11_11") (pintype "passive"))
    )
    (net (code "75") (name "unconnected-(IC2-Pad21)") (class "Default")
      (node (ref "IC2") (pin "21") (pinfunction "21_21") (pintype "passive"))
    )
    (net (code "76") (name "unconnected-(IC2-Pad22)") (class "Default")
      (node (ref "IC2") (pin "22") (pinfunction "22_22") (pintype "passive"))
    )
    (net (code "77") (name "unconnected-(IC2-Pad23)") (class "Default")
      (node (ref "IC2") (pin "23") (pinfunction "23_23") (pintype "passive"))
    )
    (net (code "78") (name "unconnected-(P1-P-Pad1)") (class "Default")
      (node (ref "P1") (pin "1") (pinfunction "P_1") (pintype "bidirectional"))
    )
    (net (code "79") (name "unconnected-(P2-P-Pad1)") (class "Default")
      (node (ref "P2") (pin "1") (pinfunction "P_1") (pintype "bidirectional"))
    )
    (net (code "80") (name "unconnected-(P3-P-Pad1)") (class "Default")
      (node (ref "P3") (pin "1") (pinfunction "P_1") (pintype "bidirectional"))
    )
    (net (code "81") (name "unconnected-(P4-P-Pad1)") (class "Default")
      (node (ref "P4") (pin "1") (pinfunction "P_1") (pintype "bidirectional"))
    )
    (net (code "82") (name "unconnected-(P5-P-Pad1)") (class "Default")
      (node (ref "P5") (pin "1") (pinfunction "P_1") (pintype "bidirectional"))
    )
    (net (code "83") (name "unconnected-(P6-P-Pad1)") (class "Default")
      (node (ref "P6") (pin "1") (pinfunction "P_1") (pintype "bidirectional"))
    )
    (net (code "84") (name "unconnected-(P7-P-Pad1)") (class "Default")
      (node (ref "P7") (pin "1") (pinfunction "P_1") (pintype "bidirectional"))
    )
    (net (code "85") (name "unconnected-(P8-P-Pad1)") (class "Default")
      (node (ref "P8") (pin "1") (pinfunction "P_1") (pintype "bidirectional"))
    )
    (net (code "86") (name "unconnected-(P9-P-Pad1)") (class "Default")
      (node (ref "P9") (pin "1") (pinfunction "P_1") (pintype "bidirectional"))
    )
    (net (code "87") (name "unconnected-(P10-P-Pad1)") (class "Default")
      (node (ref "P10") (pin "1") (pinfunction "P_1") (pintype "bidirectional"))
    )
    (net (code "88") (name "unconnected-(P11-P-Pad1)") (class "Default")
      (node (ref "P11") (pin "1") (pinfunction "P_1") (pintype "bidirectional"))
    )
    (net (code "89") (name "unconnected-(P12-P-Pad1)") (class "Default")
      (node (ref "P12") (pin "1") (pinfunction "P_1") (pintype "bidirectional"))
    )
    (net (code "90") (name "unconnected-(P13-P-Pad1)") (class "Default")
      (node (ref "P13") (pin "1") (pinfunction "P_1") (pintype "bidirectional"))
    )
    (net (code "91") (name "unconnected-(P14-P-Pad1)") (class "Default")
      (node (ref "P14") (pin "1") (pinfunction "P_1") (pintype "bidirectional"))
    )
    (net (code "92") (name "unconnected-(P15-P-Pad1)") (class "Default")
      (node (ref "P15") (pin "1") (pinfunction "P_1") (pintype "bidirectional"))
    )
    (net (code "93") (name "unconnected-(P16-P-Pad1)") (class "Default")
      (node (ref "P16") (pin "1") (pinfunction "P_1") (pintype "bidirectional"))
    )
    (net (code "94") (name "unconnected-(P17-P-Pad1)") (class "Default")
      (node (ref "P17") (pin "1") (pinfunction "P_1") (pintype "bidirectional"))
    )
    (net (code "95") (name "unconnected-(P18-P-Pad1)") (class "Default")
      (node (ref "P18") (pin "1") (pinfunction "P_1") (pintype "bidirectional"))
    )
    (net (code "96") (name "unconnected-(P19-P-Pad1)") (class "Default")
      (node (ref "P19") (pin "1") (pinfunction "P_1") (pintype "bidirectional"))
    )
    (net (code "97") (name "unconnected-(P20-P-Pad1)") (class "Default")
      (node (ref "P20") (pin "1") (pinfunction "P_1") (pintype "bidirectional"))
    )
    (net (code "98") (name "unconnected-(P21-P-Pad1)") (class "Default")
      (node (ref "P21") (pin "1") (pinfunction "P_1") (pintype "bidirectional"))
    )
    (net (code "99") (name "unconnected-(P22-P-Pad1)") (class "Default")
      (node (ref "P22") (pin "1") (pinfunction "P_1") (pintype "bidirectional"))
    )
    (net (code "100") (name "unconnected-(P23-P-Pad1)") (class "Default")
      (node (ref "P23") (pin "1") (pinfunction "P_1") (pintype "bidirectional"))
    )
    (net (code "101") (name "unconnected-(P24-P-Pad1)") (class "Default")
      (node (ref "P24") (pin "1") (pinfunction "P_1") (pintype "bidirectional"))
    )
    (net (code "102") (name "unconnected-(P25-P-Pad1)") (class "Default")
      (node (ref "P25") (pin "1") (pinfunction "P_1") (pintype "bidirectional"))
    )
    (net (code "103") (name "unconnected-(P26-P-Pad1)") (class "Default")
      (node (ref "P26") (pin "1") (pinfunction "P_1") (pintype "bidirectional"))
    )
    (net (code "104") (name "unconnected-(P27-P-Pad1)") (class "Default")
      (node (ref "P27") (pin "1") (pinfunction "P_1") (pintype "bidirectional"))
    )
    (net (code "105") (name "unconnected-(P28-P-Pad1)") (class "Default")
      (node (ref "P28") (pin "1") (pinfunction "P_1") (pintype "bidirectional"))
    )
    (net (code "106") (name "unconnected-(P29-P-Pad1)") (class "Default")
      (node (ref "P29") (pin "1") (pinfunction "P_1") (pintype "bidirectional"))
    )
    (net (code "107") (name "unconnected-(P30-P-Pad1)") (class "Default")
      (node (ref "P30") (pin "1") (pinfunction "P_1") (pintype "bidirectional"))
    )
    (net (code "108") (name "unconnected-(P31-P-Pad1)") (class "Default")
      (node (ref "P31") (pin "1") (pinfunction "P_1") (pintype "bidirectional"))
    )
    (net (code "109") (name "unconnected-(P32-P-Pad1)") (class "Default")
      (node (ref "P32") (pin "1") (pinfunction "P_1") (pintype "bidirectional"))
    )
    (net (code "110") (name "unconnected-(X2-PadGND)") (class "Default")
      (node (ref "X2") (pin "GND") (pinfunction "GND_GND") (pintype "no_connect"))
    )
  )
)
